# MS.net
KiCad netlist of a schematic drawn in EAGLE
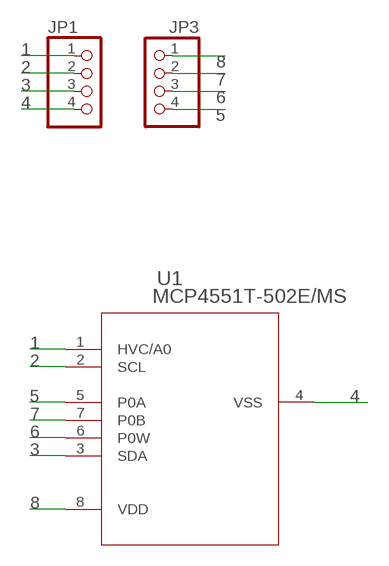
[diagram p0: schematic, sheet 1]

(export (version "E")
  (design (tool "Eeschema 10.0.6"))
  (components
    (comp (ref "JP1")
      (value "PINHD-1X4")
      (footprint "eagle-import:1X04")
      (libsource (lib "eagle-import") (part "PINHD-1X4"))
    )
    (comp (ref "JP3")
      (value "PINHD-1X4")
      (footprint "eagle-import:1X04")
      (libsource (lib "eagle-import") (part "PINHD-1X4"))
    )
    (comp (ref "U1")
      (value "MCP4551T-502E/MS")
      (footprint "eagle-import:MSOP8_MC_MCH")
      (libsource (lib "eagle-import") (part "MCP4551T-502E/MS"))
    )
  )
  (nets
    (net (code "1") (name "/1") (class "Default")
      (node (ref "JP1") (pin "1") (pinfunction "1_1") (pintype "passive"))
      (node (ref "U1") (pin "1") (pinfunction "HVC/A0_1") (pintype "input"))
    )
    (net (code "2") (name "/2") (class "Default")
      (node (ref "JP1") (pin "2") (pinfunction "2_2") (pintype "passive"))
      (node (ref "U1") (pin "2") (pinfunction "SCL_2") (pintype "input"))
    )
    (net (code "3") (name "/3") (class "Default")
      (node (ref "JP1") (pin "3") (pinfunction "3_3") (pintype "passive"))
      (node (ref "U1") (pin "3") (pinfunction "SDA_3") (pintype "bidirectional"))
    )
    (net (code "4") (name "/4") (class "Default")
      (node (ref "JP1") (pin "4") (pinfunction "4_4") (pintype "passive"))
      (node (ref "U1") (pin "4") (pinfunction "VSS_4") (pintype "power_in"))
    )
    (net (code "5") (name "/5") (class "Default")
      (node (ref "JP3") (pin "4") (pinfunction "4_4") (pintype "passive"))
      (node (ref "U1") (pin "5") (pinfunction "P0A_5") (pintype "passive"))
    )
    (net (code "6") (name "/6") (class "Default")
      (node (ref "JP3") (pin "3") (pinfunction "3_3") (pintype "passive"))
      (node (ref "U1") (pin "6") (pinfunction "P0W_6") (pintype "passive"))
    )
    (net (code "7") (name "/7") (class "Default")
      (node (ref "JP3") (pin "2") (pinfunction "2_2") (pintype "passive"))
      (node (ref "U1") (pin "7") (pinfunction "P0B_7") (pintype "passive"))
    )
    (net (code "8") (name "/8") (class "Default")
      (node (ref "JP3") (pin "1") (pinfunction "1_1") (pintype "passive"))
      (node (ref "U1") (pin "8") (pinfunction "VDD_8") (pintype "power_in"))
    )
  )
)
